# MAIN.net
KiCad netlist of a schematic drawn in Altium Designer
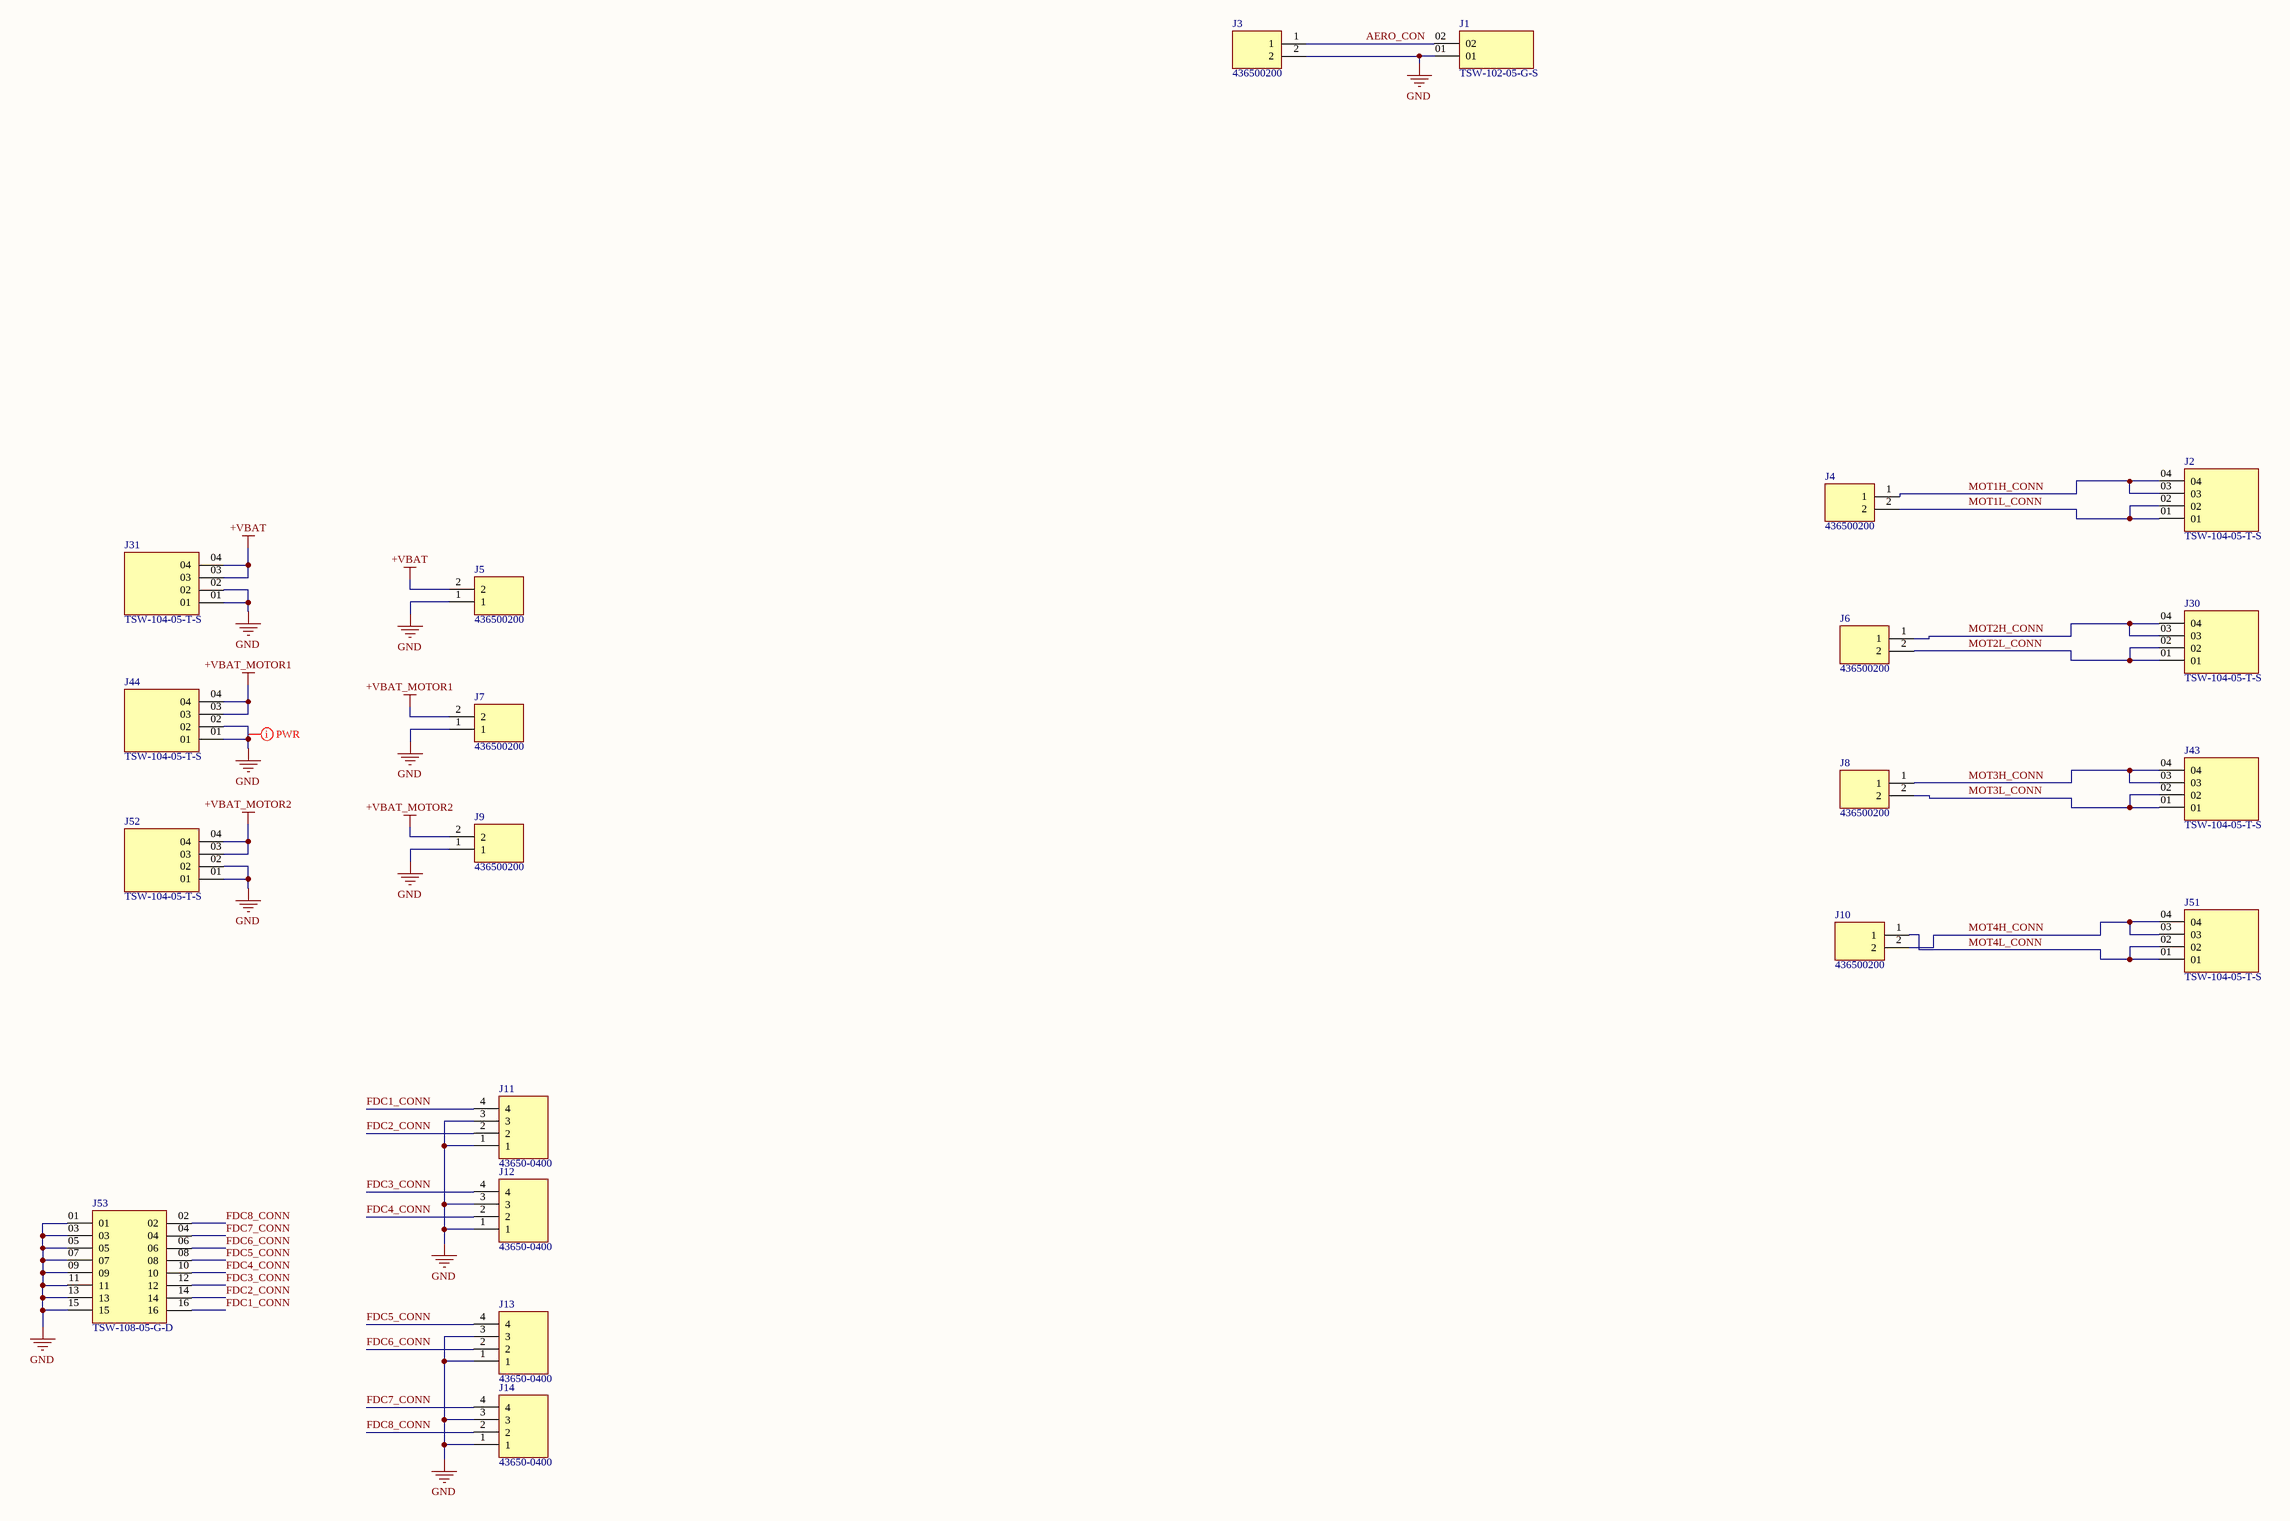
[diagram p0: MAIN.SchDoc]

(export (version "E")
  (design (tool "Eeschema 10.0.6"))
  (components
    (comp (ref "J1")
      (value "TSW-102-05-G-S")
      (footprint "TSW-102-05-G-S:SAMTEC_TSW-102-05-G-S")
      (fields (field (name "MF") "{'manufacturer': u'Samtec Inc.'}"))
      (libsource (lib "*") (part "TSW-102-05-G-S"))
    )
    (comp (ref "J2")
      (value "TSW-104-05-T-S")
      (footprint "TSW-104-05-T-S:SAMTEC_TSW-104-05-T-S")
      (fields (field (name "MF") "{'manufacturer': u'Samtec'}"))
      (libsource (lib "") (part "TSW-104-05-T-S_1"))
    )
    (comp (ref "J3")
      (value "436500200")
      (footprint "SamacSys:4365002YY_4")
      (description "Connector")
      (libsource (lib "*") (part "436500200"))
    )
    (comp (ref "J4")
      (value "436500200")
      (footprint "SamacSys:4365002YY_4")
      (description "Connector")
      (libsource (lib "*") (part "436500200"))
    )
    (comp (ref "J5")
      (value "436500200")
      (footprint "SamacSys:4365002YY_4")
      (description "Connector")
      (libsource (lib "") (part "436500200_1"))
    )
    (comp (ref "J6")
      (value "436500200")
      (footprint "SamacSys:4365002YY_4")
      (description "Connector")
      (libsource (lib "*") (part "436500200"))
    )
    (comp (ref "J7")
      (value "436500200")
      (footprint "SamacSys:4365002YY_4")
      (description "Connector")
      (libsource (lib "") (part "436500200_1"))
    )
    (comp (ref "J8")
      (value "436500200")
      (footprint "SamacSys:4365002YY_4")
      (description "Connector")
      (libsource (lib "*") (part "436500200"))
    )
    (comp (ref "J9")
      (value "436500200")
      (footprint "SamacSys:4365002YY_4")
      (description "Connector")
      (libsource (lib "") (part "436500200_1"))
    )
    (comp (ref "J10")
      (value "436500200")
      (footprint "SamacSys:4365002YY_4")
      (description "Connector")
      (libsource (lib "*") (part "436500200"))
    )
    (comp (ref "J11")
      (value "43650-0400")
      (footprint "SamacSys:43650-04YY_R")
      (description "Connector")
      (fields (field (name "MOUSER PART NUMBER") "538-43650-0400"))
      (libsource (lib "*") (part "43650-0400"))
    )
    (comp (ref "J12")
      (value "43650-0400")
      (footprint "SamacSys:43650-04YY_R")
      (description "Connector")
      (fields (field (name "MOUSER PART NUMBER") "538-43650-0400"))
      (libsource (lib "*") (part "43650-0400"))
    )
    (comp (ref "J13")
      (value "43650-0400")
      (footprint "SamacSys:43650-04YY_R")
      (description "Connector")
      (fields (field (name "MOUSER PART NUMBER") "538-43650-0400"))
      (libsource (lib "*") (part "43650-0400"))
    )
    (comp (ref "J14")
      (value "43650-0400")
      (footprint "SamacSys:43650-04YY_R")
      (description "Connector")
      (fields (field (name "MOUSER PART NUMBER") "538-43650-0400"))
      (libsource (lib "*") (part "43650-0400"))
    )
    (comp (ref "J30")
      (value "TSW-104-05-T-S")
      (footprint "TSW-104-05-T-S:SAMTEC_TSW-104-05-T-S")
      (fields (field (name "MF") "{'manufacturer': u'Samtec'}"))
      (libsource (lib "") (part "TSW-104-05-T-S_1"))
    )
    (comp (ref "J31")
      (value "TSW-104-05-T-S")
      (footprint "TSW-104-05-T-S:SAMTEC_TSW-104-05-T-S")
      (fields (field (name "MF") "{'manufacturer': u'Samtec'}"))
      (libsource (lib "*") (part "TSW-104-05-T-S"))
    )
    (comp (ref "J43")
      (value "TSW-104-05-T-S")
      (footprint "TSW-104-05-T-S:SAMTEC_TSW-104-05-T-S")
      (fields (field (name "MF") "{'manufacturer': u'Samtec'}"))
      (libsource (lib "") (part "TSW-104-05-T-S_1"))
    )
    (comp (ref "J44")
      (value "TSW-104-05-T-S")
      (footprint "TSW-104-05-T-S:SAMTEC_TSW-104-05-T-S")
      (fields (field (name "MF") "{'manufacturer': u'Samtec'}"))
      (libsource (lib "*") (part "TSW-104-05-T-S"))
    )
    (comp (ref "J51")
      (value "TSW-104-05-T-S")
      (footprint "TSW-104-05-T-S:SAMTEC_TSW-104-05-T-S")
      (fields (field (name "MF") "{'manufacturer': u'Samtec'}"))
      (libsource (lib "") (part "TSW-104-05-T-S_1"))
    )
    (comp (ref "J52")
      (value "TSW-104-05-T-S")
      (footprint "TSW-104-05-T-S:SAMTEC_TSW-104-05-T-S")
      (fields (field (name "MF") "{'manufacturer': u'Samtec'}"))
      (libsource (lib "*") (part "TSW-104-05-T-S"))
    )
    (comp (ref "J53")
      (value "TSW-108-05-G-D")
      (footprint "TSW-108-05-G-D:SAMTEC_TSW-108-05-G-D")
      (fields (field (name "MF") "{'manufacturer': u'Samtec'}"))
      (libsource (lib "*") (part "TSW-108-05-G-D"))
    )
  )
  (nets
    (net (code "1") (name "+VBAT") (class "Default")
      (node (ref "J31") (pin "03") (pinfunction "03_03") (pintype "passive"))
      (node (ref "J31") (pin "04") (pinfunction "04_04") (pintype "passive"))
      (node (ref "J5") (pin "2") (pinfunction "2_2") (pintype "passive"))
    )
    (net (code "2") (name "+VBAT_MOTOR1") (class "Default")
      (node (ref "J44") (pin "03") (pinfunction "03_03") (pintype "passive"))
      (node (ref "J44") (pin "04") (pinfunction "04_04") (pintype "passive"))
      (node (ref "J7") (pin "2") (pinfunction "2_2") (pintype "passive"))
    )
    (net (code "3") (name "+VBAT_MOTOR2") (class "Default")
      (node (ref "J52") (pin "03") (pinfunction "03_03") (pintype "passive"))
      (node (ref "J52") (pin "04") (pinfunction "04_04") (pintype "passive"))
      (node (ref "J9") (pin "2") (pinfunction "2_2") (pintype "passive"))
    )
    (net (code "4") (name "/AERO_CON") (class "Default")
      (node (ref "J1") (pin "02") (pinfunction "02_02") (pintype "passive"))
      (node (ref "J3") (pin "1") (pinfunction "1_1") (pintype "passive"))
    )
    (net (code "5") (name "/FDC1_CONN") (class "Default")
      (node (ref "J11") (pin "4") (pinfunction "4_4") (pintype "passive"))
      (node (ref "J53") (pin "16") (pinfunction "16_16") (pintype "passive"))
    )
    (net (code "6") (name "/FDC2_CONN") (class "Default")
      (node (ref "J11") (pin "2") (pinfunction "2_2") (pintype "passive"))
      (node (ref "J53") (pin "14") (pinfunction "14_14") (pintype "passive"))
    )
    (net (code "7") (name "/FDC3_CONN") (class "Default")
      (node (ref "J12") (pin "4") (pinfunction "4_4") (pintype "passive"))
      (node (ref "J53") (pin "12") (pinfunction "12_12") (pintype "passive"))
    )
    (net (code "8") (name "/FDC4_CONN") (class "Default")
      (node (ref "J12") (pin "2") (pinfunction "2_2") (pintype "passive"))
      (node (ref "J53") (pin "10") (pinfunction "10_10") (pintype "passive"))
    )
    (net (code "9") (name "/FDC5_CONN") (class "Default")
      (node (ref "J13") (pin "4") (pinfunction "4_4") (pintype "passive"))
      (node (ref "J53") (pin "08") (pinfunction "08_08") (pintype "passive"))
    )
    (net (code "10") (name "/FDC6_CONN") (class "Default")
      (node (ref "J13") (pin "2") (pinfunction "2_2") (pintype "passive"))
      (node (ref "J53") (pin "06") (pinfunction "06_06") (pintype "passive"))
    )
    (net (code "11") (name "/FDC7_CONN") (class "Default")
      (node (ref "J14") (pin "4") (pinfunction "4_4") (pintype "passive"))
      (node (ref "J53") (pin "04") (pinfunction "04_04") (pintype "passive"))
    )
    (net (code "12") (name "/FDC8_CONN") (class "Default")
      (node (ref "J14") (pin "2") (pinfunction "2_2") (pintype "passive"))
      (node (ref "J53") (pin "02") (pinfunction "02_02") (pintype "passive"))
    )
    (net (code "13") (name "/MOT1H_CONN") (class "Default")
      (node (ref "J2") (pin "03") (pinfunction "03_03") (pintype "passive"))
      (node (ref "J2") (pin "04") (pinfunction "04_04") (pintype "passive"))
      (node (ref "J4") (pin "1") (pinfunction "1_1") (pintype "passive"))
    )
    (net (code "14") (name "/MOT1L_CONN") (class "Default")
      (node (ref "J2") (pin "01") (pinfunction "01_01") (pintype "passive"))
      (node (ref "J2") (pin "02") (pinfunction "02_02") (pintype "passive"))
      (node (ref "J4") (pin "2") (pinfunction "2_2") (pintype "passive"))
    )
    (net (code "15") (name "/MOT2H_CONN") (class "Default")
      (node (ref "J30") (pin "03") (pinfunction "03_03") (pintype "passive"))
      (node (ref "J30") (pin "04") (pinfunction "04_04") (pintype "passive"))
      (node (ref "J6") (pin "1") (pinfunction "1_1") (pintype "passive"))
    )
    (net (code "16") (name "/MOT2L_CONN") (class "Default")
      (node (ref "J30") (pin "01") (pinfunction "01_01") (pintype "passive"))
      (node (ref "J30") (pin "02") (pinfunction "02_02") (pintype "passive"))
      (node (ref "J6") (pin "2") (pinfunction "2_2") (pintype "passive"))
    )
    (net (code "17") (name "/MOT3H_CONN") (class "Default")
      (node (ref "J43") (pin "03") (pinfunction "03_03") (pintype "passive"))
      (node (ref "J43") (pin "04") (pinfunction "04_04") (pintype "passive"))
      (node (ref "J8") (pin "1") (pinfunction "1_1") (pintype "passive"))
    )
    (net (code "18") (name "/MOT3L_CONN") (class "Default")
      (node (ref "J43") (pin "01") (pinfunction "01_01") (pintype "passive"))
      (node (ref "J43") (pin "02") (pinfunction "02_02") (pintype "passive"))
      (node (ref "J8") (pin "2") (pinfunction "2_2") (pintype "passive"))
    )
    (net (code "19") (name "/MOT4H_CONN") (class "Default")
      (node (ref "J10") (pin "2") (pinfunction "2_2") (pintype "passive"))
      (node (ref "J51") (pin "03") (pinfunction "03_03") (pintype "passive"))
      (node (ref "J51") (pin "04") (pinfunction "04_04") (pintype "passive"))
    )
    (net (code "20") (name "/MOT4L_CONN") (class "Default")
      (node (ref "J10") (pin "1") (pinfunction "1_1") (pintype "passive"))
      (node (ref "J51") (pin "01") (pinfunction "01_01") (pintype "passive"))
      (node (ref "J51") (pin "02") (pinfunction "02_02") (pintype "passive"))
    )
    (net (code "21") (name "GND") (class "Default")
      (node (ref "J1") (pin "01") (pinfunction "01_01") (pintype "passive"))
      (node (ref "J11") (pin "1") (pinfunction "1_1") (pintype "passive"))
      (node (ref "J11") (pin "3") (pinfunction "3_3") (pintype "passive"))
      (node (ref "J12") (pin "1") (pinfunction "1_1") (pintype "passive"))
      (node (ref "J12") (pin "3") (pinfunction "3_3") (pintype "passive"))
      (node (ref "J13") (pin "1") (pinfunction "1_1") (pintype "passive"))
      (node (ref "J13") (pin "3") (pinfunction "3_3") (pintype "passive"))
      (node (ref "J14") (pin "1") (pinfunction "1_1") (pintype "passive"))
      (node (ref "J14") (pin "3") (pinfunction "3_3") (pintype "passive"))
      (node (ref "J3") (pin "2") (pinfunction "2_2") (pintype "passive"))
      (node (ref "J31") (pin "01") (pinfunction "01_01") (pintype "passive"))
      (node (ref "J31") (pin "02") (pinfunction "02_02") (pintype "passive"))
      (node (ref "J44") (pin "01") (pinfunction "01_01") (pintype "passive"))
      (node (ref "J44") (pin "02") (pinfunction "02_02") (pintype "passive"))
      (node (ref "J5") (pin "1") (pinfunction "1_1") (pintype "passive"))
      (node (ref "J52") (pin "01") (pinfunction "01_01") (pintype "passive"))
      (node (ref "J52") (pin "02") (pinfunction "02_02") (pintype "passive"))
      (node (ref "J53") (pin "01") (pinfunction "01_01") (pintype "passive"))
      (node (ref "J53") (pin "03") (pinfunction "03_03") (pintype "passive"))
      (node (ref "J53") (pin "05") (pinfunction "05_05") (pintype "passive"))
      (node (ref "J53") (pin "07") (pinfunction "07_07") (pintype "passive"))
      (node (ref "J53") (pin "09") (pinfunction "09_09") (pintype "passive"))
      (node (ref "J53") (pin "11") (pinfunction "11_11") (pintype "passive"))
      (node (ref "J53") (pin "13") (pinfunction "13_13") (pintype "passive"))
      (node (ref "J53") (pin "15") (pinfunction "15_15") (pintype "passive"))
      (node (ref "J7") (pin "1") (pinfunction "1_1") (pintype "passive"))
      (node (ref "J9") (pin "1") (pinfunction "1_1") (pintype "passive"))
    )
  )
)
